# positioningAndThermistor.net
KiCad netlist of a schematic drawn in Altium Designer
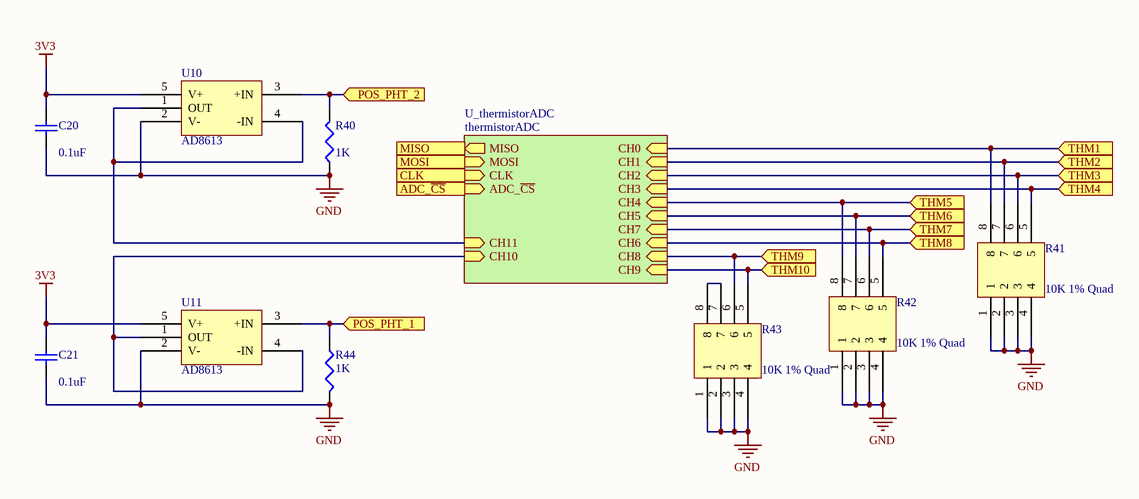
[diagram p0: positioningAndThermistor.SchDoc]

(export (version "E")
  (design (tool "Eeschema 10.0.6"))
  (components
    (comp (ref "C20")
      (value "0.1uF")
      (footprint "1608[0603]")
      (description "Capacitor (Semiconductor SIM Model)")
      (fields (field (name "PUBLISHER") "Altium Limited"))
      (libsource (lib "Miscellaneous Devices") (part "Cap Semi"))
    )
    (comp (ref "C21")
      (value "0.1uF")
      (footprint "1608[0603]")
      (description "Capacitor (Semiconductor SIM Model)")
      (fields (field (name "PUBLISHER") "Altium Limited"))
      (libsource (lib "Miscellaneous Devices") (part "Cap Semi"))
    )
    (comp (ref "R40")
      (value "1K")
      (footprint "J1-0603")
      (description "Resistor")
      (fields (field (name "PUBLISHER") "Altium Limited"))
      (libsource (lib "Miscellaneous Devices") (part "Res3"))
    )
    (comp (ref "R41")
      (value "10K 1% Quad")
      (footprint "ResQuad-320X150")
      (description "Quad pack resistor")
      (libsource (lib "PAY") (part "Res Quad Pack"))
    )
    (comp (ref "R42")
      (value "10K 1% Quad")
      (footprint "ResQuad-320X150")
      (description "Quad pack resistor")
      (libsource (lib "PAY") (part "Res Quad Pack"))
    )
    (comp (ref "R43")
      (value "10K 1% Quad")
      (footprint "ResQuad-320X150")
      (description "Quad pack resistor")
      (libsource (lib "PAY") (part "Res Quad Pack"))
    )
    (comp (ref "R44")
      (value "1K")
      (footprint "J1-0603")
      (description "Resistor")
      (fields (field (name "PUBLISHER") "Altium Limited"))
      (libsource (lib "Miscellaneous Devices") (part "Res3"))
    )
    (comp (ref "U10")
      (value "AD8613")
      (footprint "SOP-65P200X125-5N")
      (description "Low power, low noise rail-to-rail op-amp.")
      (libsource (lib "PAY") (part "AD8613"))
    )
    (comp (ref "U11")
      (value "AD8613")
      (footprint "SOP-65P200X125-5N")
      (description "Low power, low noise rail-to-rail op-amp.")
      (libsource (lib "PAY") (part "AD8613"))
    )
  )
  (nets
    (net (code "2") (name "/CH10") (class "Default")
      (node (ref "U11") (pin "1") (pinfunction "OUT_1") (pintype "passive"))
      (node (ref "U11") (pin "4") (pinfunction "-IN_4") (pintype "passive"))
    )
    (net (code "3") (name "/CH11") (class "Default")
      (node (ref "U10") (pin "1") (pinfunction "OUT_1") (pintype "passive"))
      (node (ref "U10") (pin "4") (pinfunction "-IN_4") (pintype "passive"))
    )
    (net (code "7") (name "/POS_PHT_1") (class "Default")
      (node (ref "R44") (pin "1") (pinfunction "1_1") (pintype "passive"))
      (node (ref "U11") (pin "3") (pinfunction "+IN_3") (pintype "passive"))
    )
    (net (code "8") (name "/POS_PHT_2") (class "Default")
      (node (ref "R40") (pin "2") (pinfunction "2_2") (pintype "passive"))
      (node (ref "U10") (pin "3") (pinfunction "+IN_3") (pintype "passive"))
    )
    (net (code "9") (name "/THM1") (class "Default")
      (node (ref "R41") (pin "8") (pinfunction "8_8") (pintype "passive"))
    )
    (net (code "10") (name "/THM2") (class "Default")
      (node (ref "R41") (pin "7") (pinfunction "7_7") (pintype "passive"))
    )
    (net (code "11") (name "/THM3") (class "Default")
      (node (ref "R41") (pin "6") (pinfunction "6_6") (pintype "passive"))
    )
    (net (code "12") (name "/THM4") (class "Default")
      (node (ref "R41") (pin "5") (pinfunction "5_5") (pintype "passive"))
    )
    (net (code "13") (name "/THM5") (class "Default")
      (node (ref "R42") (pin "8") (pinfunction "8_8") (pintype "passive"))
    )
    (net (code "14") (name "/THM6") (class "Default")
      (node (ref "R42") (pin "7") (pinfunction "7_7") (pintype "passive"))
    )
    (net (code "15") (name "/THM7") (class "Default")
      (node (ref "R42") (pin "6") (pinfunction "6_6") (pintype "passive"))
    )
    (net (code "16") (name "/THM8") (class "Default")
      (node (ref "R42") (pin "5") (pinfunction "5_5") (pintype "passive"))
    )
    (net (code "17") (name "/THM9") (class "Default")
      (node (ref "R43") (pin "6") (pinfunction "6_6") (pintype "passive"))
    )
    (net (code "18") (name "/THM10") (class "Default")
      (node (ref "R43") (pin "5") (pinfunction "5_5") (pintype "passive"))
    )
    (net (code "19") (name "3V3") (class "Default")
      (node (ref "C20") (pin "2") (pinfunction "2_2") (pintype "passive"))
      (node (ref "C21") (pin "2") (pinfunction "2_2") (pintype "passive"))
      (node (ref "U10") (pin "5") (pinfunction "V+_5") (pintype "passive"))
      (node (ref "U11") (pin "5") (pinfunction "V+_5") (pintype "passive"))
    )
    (net (code "20") (name "GND") (class "Default")
      (node (ref "C20") (pin "1") (pinfunction "1_1") (pintype "passive"))
      (node (ref "C21") (pin "1") (pinfunction "1_1") (pintype "passive"))
      (node (ref "R40") (pin "1") (pinfunction "1_1") (pintype "passive"))
      (node (ref "R41") (pin "1") (pinfunction "1_1") (pintype "passive"))
      (node (ref "R41") (pin "2") (pinfunction "2_2") (pintype "passive"))
      (node (ref "R41") (pin "3") (pinfunction "3_3") (pintype "passive"))
      (node (ref "R41") (pin "4") (pinfunction "4_4") (pintype "passive"))
      (node (ref "R42") (pin "1") (pinfunction "1_1") (pintype "passive"))
      (node (ref "R42") (pin "2") (pinfunction "2_2") (pintype "passive"))
      (node (ref "R42") (pin "3") (pinfunction "3_3") (pintype "passive"))
      (node (ref "R42") (pin "4") (pinfunction "4_4") (pintype "passive"))
      (node (ref "R43") (pin "1") (pinfunction "1_1") (pintype "passive"))
      (node (ref "R43") (pin "2") (pinfunction "2_2") (pintype "passive"))
      (node (ref "R43") (pin "3") (pinfunction "3_3") (pintype "passive"))
      (node (ref "R43") (pin "4") (pinfunction "4_4") (pintype "passive"))
      (node (ref "R44") (pin "2") (pinfunction "2_2") (pintype "passive"))
      (node (ref "U10") (pin "2") (pinfunction "V-_2") (pintype "passive"))
      (node (ref "U11") (pin "2") (pinfunction "V-_2") (pintype "passive"))
    )
    (net (code "21") (name "Net-(R43-Pad7)") (class "Default")
      (node (ref "R43") (pin "7") (pinfunction "7_7") (pintype "passive"))
      (node (ref "R43") (pin "8") (pinfunction "8_8") (pintype "passive"))
    )
  )
)
